# SmellSprayer.net
KiCad netlist of a schematic drawn in EAGLE
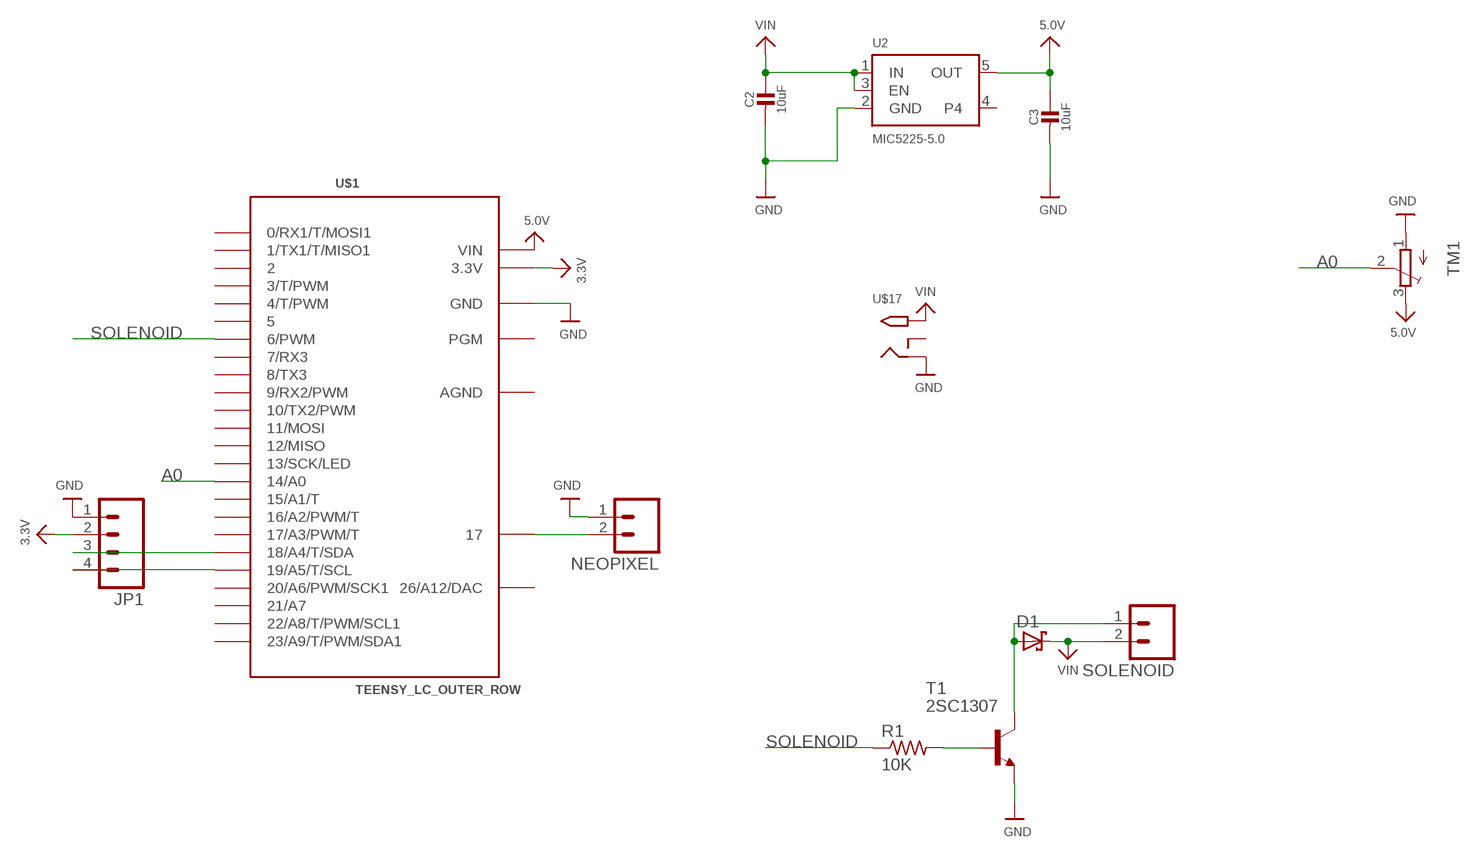
[diagram p0: schematic, sheet 1]

(export (version "E")
  (design (tool "Eeschema 10.0.6"))
  (components
    (comp (ref "C2")
      (value "10uF")
      (footprint "eagle-import:0805-NO")
      (libsource (lib "eagle-import") (part "CAP_CERAMIC0805-NOOUTLINE"))
    )
    (comp (ref "C3")
      (value "10uF")
      (footprint "eagle-import:0805-NO")
      (libsource (lib "eagle-import") (part "CAP_CERAMIC0805-NOOUTLINE"))
    )
    (comp (ref "D1")
      (value "SCHOTTKY-DIODEDO41-7")
      (footprint "eagle-import:DO41-7")
      (libsource (lib "eagle-import") (part "SCHOTTKY-DIODEDO41-7"))
    )
    (comp (ref "JP1")
      (value "M04POLAR")
      (footprint "eagle-import:MOLEX-1X4")
      (libsource (lib "eagle-import") (part "M04POLAR"))
    )
    (comp (ref "NEOPIXEL")
      (value "M02POLAR")
      (footprint "eagle-import:MOLEX-1X2")
      (libsource (lib "eagle-import") (part "M02POLAR"))
    )
    (comp (ref "R1")
      (value "10K")
      (footprint "eagle-import:R0805")
      (libsource (lib "eagle-import") (part "R-US_R0805"))
    )
    (comp (ref "SOLENOID")
      (value "M023.5MM_LOCK")
      (footprint "eagle-import:SCREWTERMINAL-3.5MM-2_LOCK")
      (libsource (lib "eagle-import") (part "M023.5MM_LOCK"))
    )
    (comp (ref "T1")
      (value "2SC1307")
      (footprint "eagle-import:TO220AV")
      (libsource (lib "eagle-import") (part "2SC1307"))
    )
    (comp (ref "TM1")
      (value "TRIMPOT3386")
      (footprint "eagle-import:TRIM-3386")
      (libsource (lib "eagle-import") (part "TRIMPOT3386"))
    )
    (comp (ref "U$1")
      (value "TEENSY_LC_OUTER_ROW")
      (footprint "eagle-import:TEENSY3-OUTER_ROW")
      (libsource (lib "eagle-import") (part "TEENSY_LC_OUTER_ROW"))
    )
    (comp (ref "U$17")
      (value "2.1MMJACKSMT")
      (footprint "eagle-import:DCJACK_2MM_SMT")
      (libsource (lib "eagle-import") (part "2.1MMJACKSMT"))
    )
    (comp (ref "U2")
      (value "MIC5225-5.0")
      (footprint "eagle-import:SOT23-5")
      (libsource (lib "eagle-import") (part "VREG_SOT23-5"))
    )
  )
  (nets
    (net (code "1") (name "/26{slash}A12{slash}DAC") (class "Default")
      (node (ref "U$1") (pin "RESET/DAC") (pinfunction "26/A12/DAC_RESET/DAC") (pintype "power_in"))
    )
    (net (code "2") (name "/A0") (class "Default")
      (node (ref "TM1") (pin "2") (pinfunction "S_2") (pintype "passive"))
      (node (ref "U$1") (pin "14/A0") (pinfunction "14/A0_14/A0") (pintype "bidirectional"))
    )
    (net (code "3") (name "/AGND") (class "Default")
      (node (ref "U$1") (pin "AGND") (pinfunction "AGND_AGND") (pintype "power_in"))
    )
    (net (code "4") (name "/SOLENOID") (class "Default")
      (node (ref "R1") (pin "1") (pinfunction "1_1") (pintype "passive"))
      (node (ref "U$1") (pin "6") (pinfunction "6/PWM_6") (pintype "bidirectional"))
    )
    (net (code "5") (name "3.3V") (class "Default")
      (node (ref "JP1") (pin "2") (pinfunction "2_2") (pintype "passive"))
      (node (ref "U$1") (pin "3.3V") (pinfunction "3.3V_3.3V") (pintype "power_in"))
      (node (ref "U$1") (pin "3.3V1") (pinfunction "3.3V_3.3V1") (pintype "power_in"))
    )
    (net (code "6") (name "5.0V") (class "Default")
      (node (ref "C3") (pin "1") (pinfunction "1_1") (pintype "passive"))
      (node (ref "TM1") (pin "3") (pinfunction "E_3") (pintype "passive"))
      (node (ref "U$1") (pin "VIN") (pinfunction "VIN_VIN") (pintype "power_in"))
      (node (ref "U2") (pin "5") (pinfunction "OUT_5") (pintype "power_in"))
    )
    (net (code "7") (name "GND") (class "Default")
      (node (ref "C2") (pin "2") (pinfunction "2_2") (pintype "passive"))
      (node (ref "C3") (pin "2") (pinfunction "2_2") (pintype "passive"))
      (node (ref "JP1") (pin "1") (pinfunction "1_1") (pintype "passive"))
      (node (ref "NEOPIXEL") (pin "1") (pinfunction "1_1") (pintype "passive"))
      (node (ref "T1") (pin "3") (pinfunction "E_3") (pintype "passive"))
      (node (ref "TM1") (pin "1") (pinfunction "A_1") (pintype "passive"))
      (node (ref "U$1") (pin "GND") (pinfunction "GND_GND") (pintype "power_in"))
      (node (ref "U$1") (pin "GND1") (pinfunction "GND_GND1") (pintype "power_in"))
      (node (ref "U$17") (pin "GND") (pinfunction "RING_GND") (pintype "bidirectional"))
      (node (ref "U2") (pin "2") (pinfunction "GND_2") (pintype "power_in"))
    )
    (net (code "8") (name "Net-(T1-B)") (class "Default")
      (node (ref "R1") (pin "2") (pinfunction "2_2") (pintype "passive"))
      (node (ref "T1") (pin "1") (pinfunction "B_1") (pintype "passive"))
    )
    (net (code "9") (name "Net-(T1-C)") (class "Default")
      (node (ref "D1") (pin "A") (pinfunction "A_A") (pintype "passive"))
      (node (ref "SOLENOID") (pin "1") (pinfunction "1_1") (pintype "passive"))
      (node (ref "T1") (pin "2") (pinfunction "C_2") (pintype "passive"))
    )
    (net (code "10") (name "Net-(U$1-17)") (class "Default")
      (node (ref "NEOPIXEL") (pin "2") (pinfunction "2_2") (pintype "passive"))
      (node (ref "U$1") (pin "VBAT") (pinfunction "17_VBAT") (pintype "bidirectional"))
    )
    (net (code "11") (name "Net-(U$1-18{slash}A4{slash}T{slash}SDA)") (class "Default")
      (node (ref "JP1") (pin "3") (pinfunction "3_3") (pintype "passive"))
      (node (ref "U$1") (pin "18/A4") (pinfunction "18/A4/T/SDA_18/A4") (pintype "bidirectional"))
    )
    (net (code "12") (name "Net-(U$1-19{slash}A5{slash}T{slash}SCL)") (class "Default")
      (node (ref "JP1") (pin "4") (pinfunction "4_4") (pintype "passive"))
      (node (ref "U$1") (pin "19/A5") (pinfunction "19/A5/T/SCL_19/A5") (pintype "bidirectional"))
    )
    (net (code "13") (name "VIN") (class "Default")
      (node (ref "C2") (pin "1") (pinfunction "1_1") (pintype "passive"))
      (node (ref "D1") (pin "C") (pinfunction "C_C") (pintype "passive"))
      (node (ref "SOLENOID") (pin "2") (pinfunction "2_2") (pintype "passive"))
      (node (ref "U$17") (pin "PWR2") (pinfunction "TIP_PWR2") (pintype "bidirectional"))
      (node (ref "U2") (pin "1") (pinfunction "IN_1") (pintype "power_in"))
      (node (ref "U2") (pin "3") (pinfunction "EN_3") (pintype "input"))
    )
    (net (code "14") (name "unconnected-(U$1-0{slash}RX1{slash}T{slash}MOSI1-Pad0)") (class "Default")
      (node (ref "U$1") (pin "0") (pinfunction "0/RX1/T/MOSI1_0") (pintype "bidirectional"))
    )
    (net (code "15") (name "unconnected-(U$1-1{slash}TX1{slash}T{slash}MISO1-Pad1)") (class "Default")
      (node (ref "U$1") (pin "1") (pinfunction "1/TX1/T/MISO1_1") (pintype "bidirectional"))
    )
    (net (code "16") (name "unconnected-(U$1-3{slash}T{slash}PWM-Pad3)") (class "Default")
      (node (ref "U$1") (pin "3") (pinfunction "3/T/PWM_3") (pintype "bidirectional"))
    )
    (net (code "17") (name "unconnected-(U$1-4{slash}T{slash}PWM-Pad4)") (class "Default")
      (node (ref "U$1") (pin "4") (pinfunction "4/T/PWM_4") (pintype "bidirectional"))
    )
    (net (code "18") (name "unconnected-(U$1-7{slash}RX3-Pad7)") (class "Default")
      (node (ref "U$1") (pin "7") (pinfunction "7/RX3_7") (pintype "bidirectional"))
    )
    (net (code "19") (name "unconnected-(U$1-8{slash}TX3-Pad8)") (class "Default")
      (node (ref "U$1") (pin "8") (pinfunction "8/TX3_8") (pintype "bidirectional"))
    )
    (net (code "20") (name "unconnected-(U$1-9{slash}RX2{slash}PWM-Pad9)") (class "Default")
      (node (ref "U$1") (pin "9") (pinfunction "9/RX2/PWM_9") (pintype "bidirectional"))
    )
    (net (code "21") (name "unconnected-(U$1-10{slash}TX2{slash}PWM-Pad10)") (class "Default")
      (node (ref "U$1") (pin "10") (pinfunction "10/TX2/PWM_10") (pintype "bidirectional"))
    )
    (net (code "22") (name "unconnected-(U$1-11{slash}MOSI-Pad11)") (class "Default")
      (node (ref "U$1") (pin "11") (pinfunction "11/MOSI_11") (pintype "bidirectional"))
    )
    (net (code "23") (name "unconnected-(U$1-12{slash}MISO-Pad12)") (class "Default")
      (node (ref "U$1") (pin "12") (pinfunction "12/MISO_12") (pintype "bidirectional"))
    )
    (net (code "24") (name "unconnected-(U$1-13{slash}SCK{slash}LED-Pad13)") (class "Default")
      (node (ref "U$1") (pin "13") (pinfunction "13/SCK/LED_13") (pintype "bidirectional"))
    )
    (net (code "25") (name "unconnected-(U$1-15{slash}A1{slash}T-Pad15{slash}A1)") (class "Default")
      (node (ref "U$1") (pin "15/A1") (pinfunction "15/A1/T_15/A1") (pintype "bidirectional"))
    )
    (net (code "26") (name "unconnected-(U$1-16{slash}A2{slash}PWM{slash}T-Pad16{slash}A2)") (class "Default")
      (node (ref "U$1") (pin "16/A2") (pinfunction "16/A2/PWM/T_16/A2") (pintype "bidirectional"))
    )
    (net (code "27") (name "unconnected-(U$1-17{slash}A3{slash}PWM{slash}T-Pad17{slash}A3)") (class "Default")
      (node (ref "U$1") (pin "17/A3") (pinfunction "17/A3/PWM/T_17/A3") (pintype "bidirectional"))
    )
    (net (code "28") (name "unconnected-(U$1-20{slash}A6{slash}PWM{slash}SCK1-Pad20{slash}A6)") (class "Default")
      (node (ref "U$1") (pin "20/A6") (pinfunction "20/A6/PWM/SCK1_20/A6") (pintype "bidirectional"))
    )
    (net (code "29") (name "unconnected-(U$1-22{slash}A8{slash}T{slash}PWM{slash}SCL1-Pad22{slash}A8)") (class "Default")
      (node (ref "U$1") (pin "22/A8") (pinfunction "22/A8/T/PWM/SCL1_22/A8") (pintype "bidirectional"))
    )
    (net (code "30") (name "unconnected-(U$1-23{slash}A9{slash}T{slash}PWM{slash}SDA1-Pad23{slash}A9)") (class "Default")
      (node (ref "U$1") (pin "23/A9") (pinfunction "23/A9/T/PWM/SDA1_23/A9") (pintype "bidirectional"))
    )
    (net (code "31") (name "unconnected-(U$1-Pad2)") (class "Default")
      (node (ref "U$1") (pin "2") (pinfunction "2_2") (pintype "bidirectional"))
    )
    (net (code "32") (name "unconnected-(U$1-Pad5)") (class "Default")
      (node (ref "U$1") (pin "5") (pinfunction "5_5") (pintype "bidirectional"))
    )
    (net (code "33") (name "unconnected-(U$1-Pad21{slash}A7)") (class "Default")
      (node (ref "U$1") (pin "21/A7") (pinfunction "21/A7_21/A7") (pintype "bidirectional"))
    )
    (net (code "34") (name "unconnected-(U$1-PadPGM)") (class "Default")
      (node (ref "U$1") (pin "PGM") (pinfunction "PGM_PGM") (pintype "bidirectional"))
    )
    (net (code "35") (name "unconnected-(U$17-RING_SW-PadGNDBREAK)") (class "Default")
      (node (ref "U$17") (pin "GNDBREAK") (pinfunction "RING_SW_GNDBREAK") (pintype "bidirectional"))
    )
    (net (code "36") (name "unconnected-(U2-P4-Pad4)") (class "Default")
      (node (ref "U2") (pin "4") (pinfunction "P4_4") (pintype "bidirectional"))
    )
  )
)
